# C-05_LPDDR4_x.net
KiCad netlist of a schematic drawn in Altium Designer
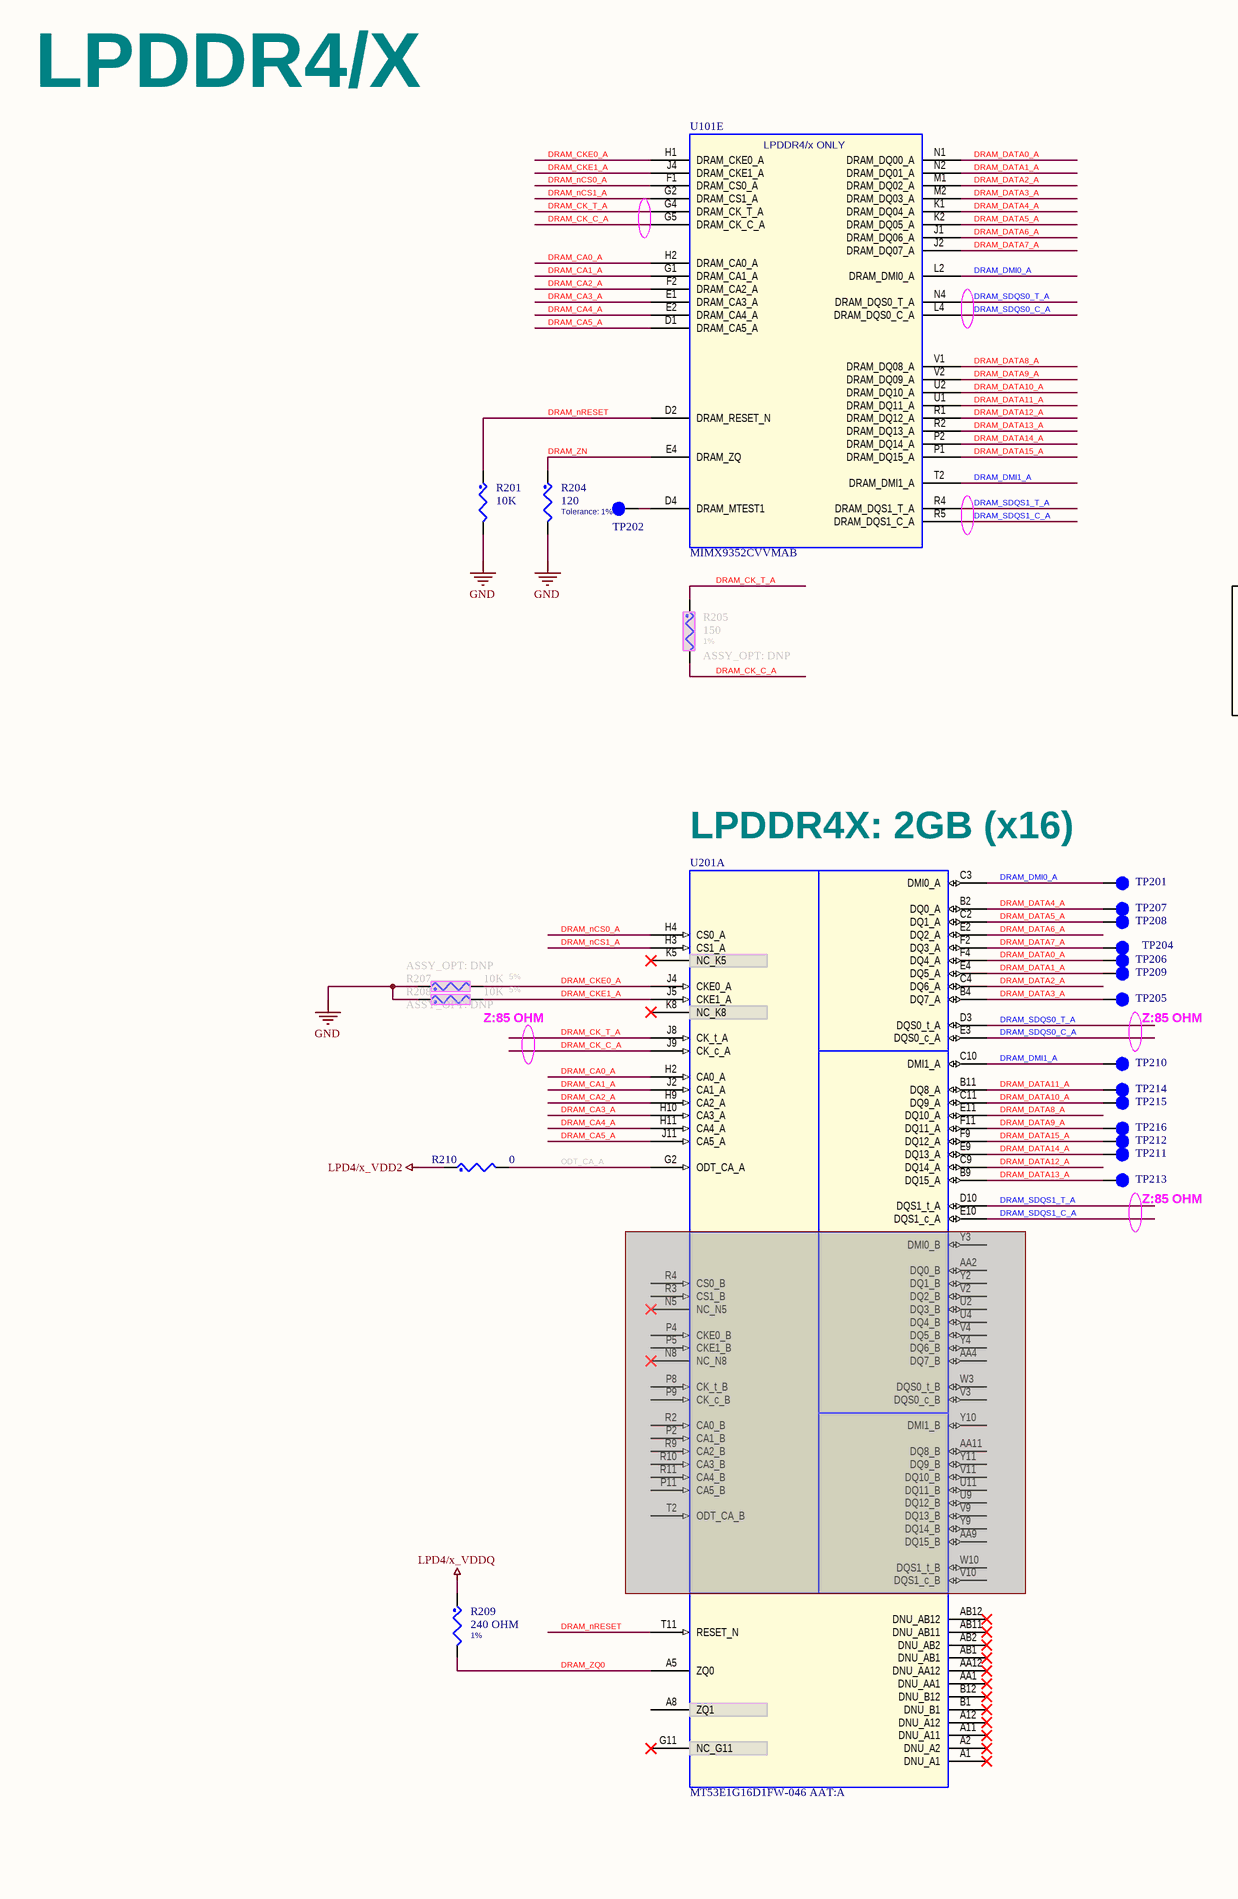
[diagram p0: C-05 LPDDR4_x.SchDoc, left]
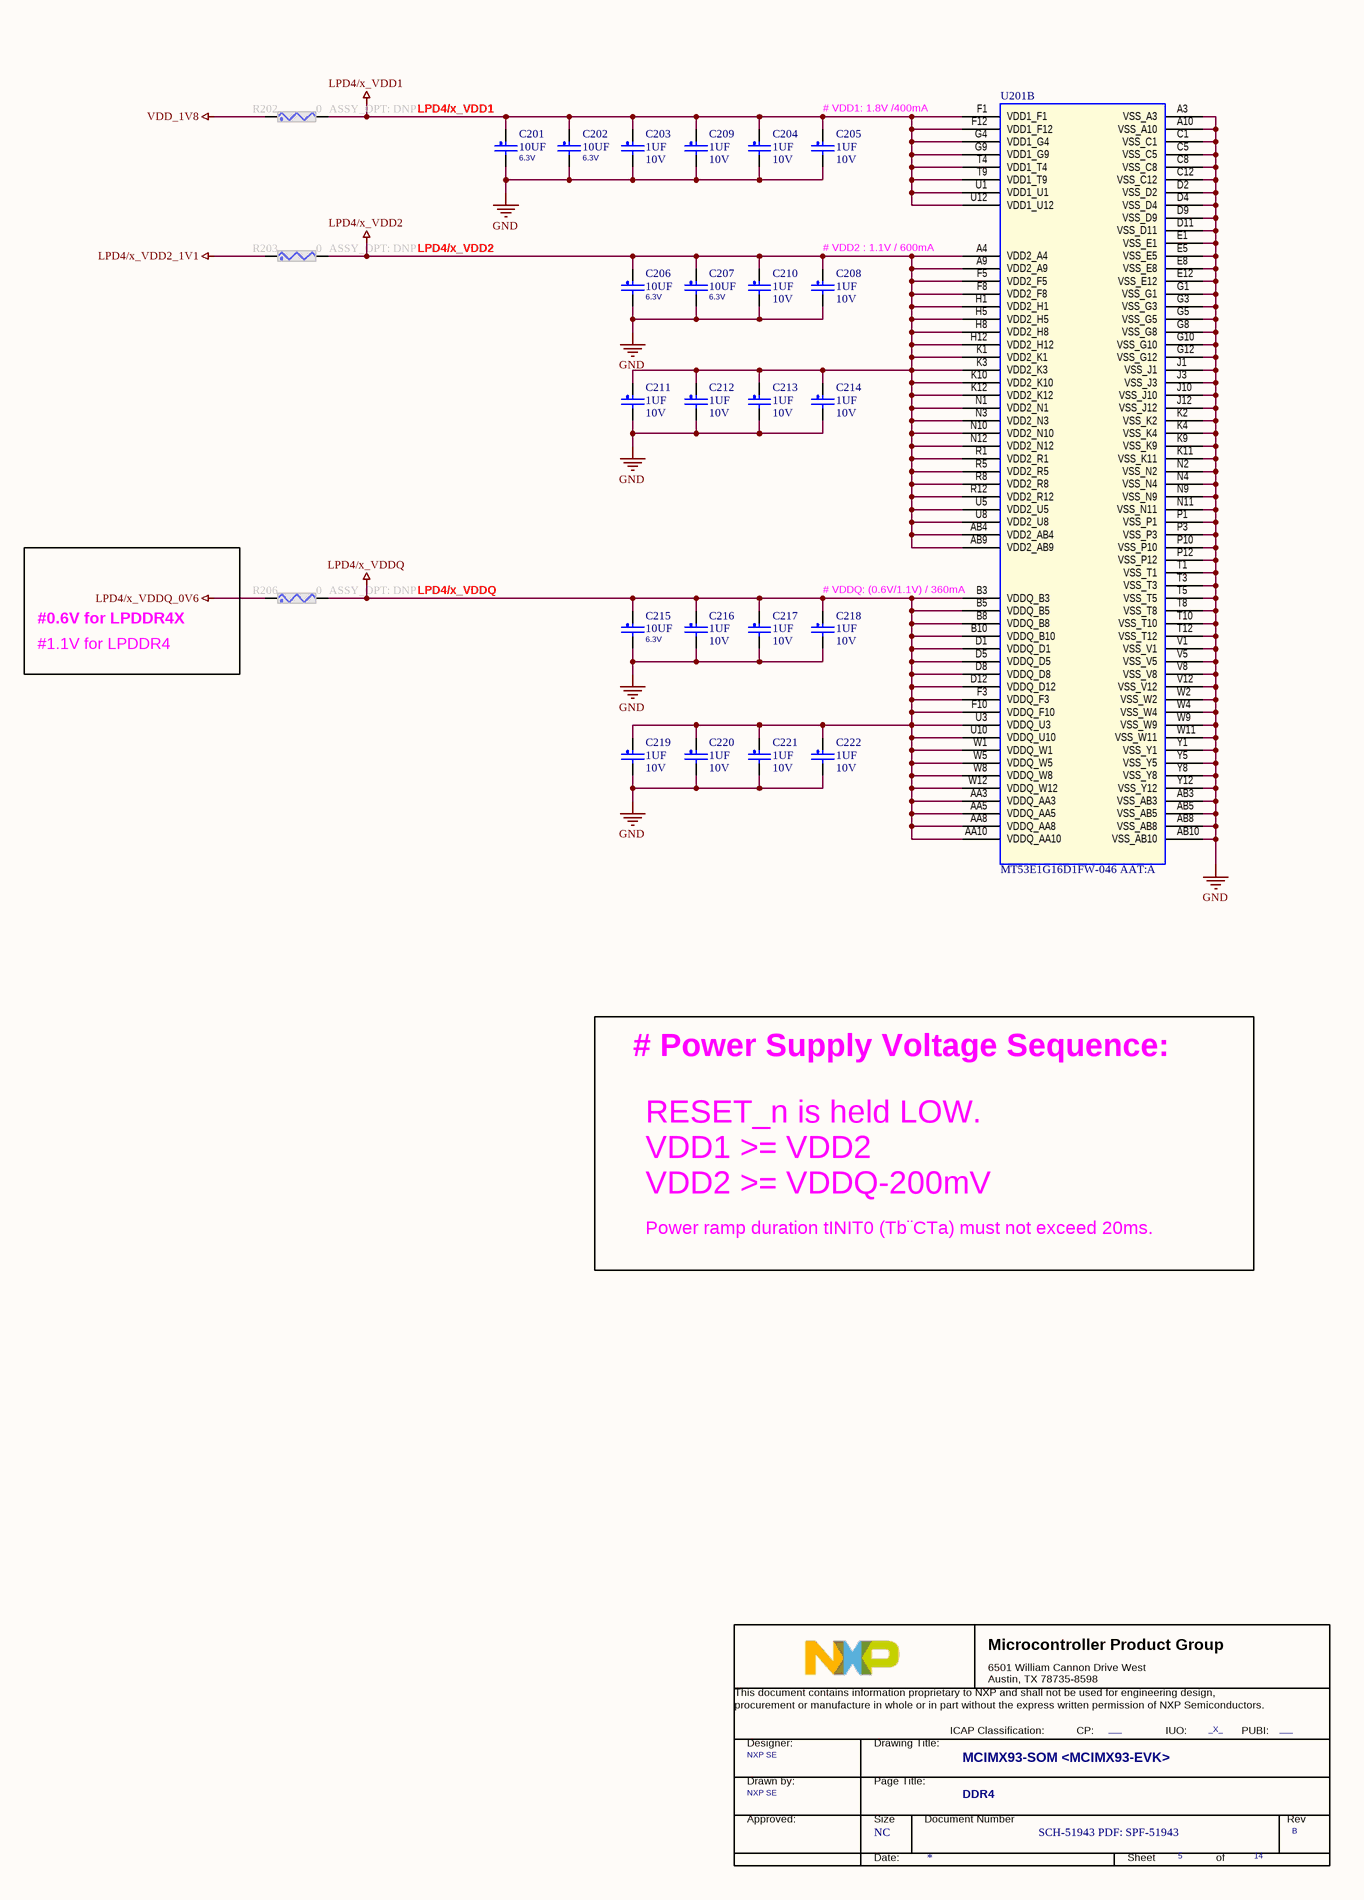
[diagram p1: C-05 LPDDR4_x.SchDoc, right]

(export (version "E")
  (design (tool "Eeschema 10.0.6"))
  (components
    (comp (ref "C201")
      (value "10UF")
      (footprint "0402_CC")
      (description "CAP CER 10UF 6.3V 20% X5R 0402")
      (fields (field (name "TOLERANCE") "20%") (field (name "VOLTAGE") "6.3V"))
      (libsource (lib "*") (part "CAP_NP"))
    )
    (comp (ref "C202")
      (value "10UF")
      (footprint "0402_CC")
      (description "CAP CER 10UF 6.3V 20% X5R 0402")
      (fields (field (name "TOLERANCE") "20%") (field (name "VOLTAGE") "6.3V"))
      (libsource (lib "*") (part "CAP_NP"))
    )
    (comp (ref "C203")
      (value "1UF")
      (footprint "0201_CC")
      (description "CAP CER 1.0uF 10V 10% X5R 0201")
      (fields (field (name "VOLTAGE") "10V") (field (name "TOLERANCE") "10%"))
      (libsource (lib "*") (part "CAP_NP"))
    )
    (comp (ref "C204")
      (value "1UF")
      (footprint "0201_CC")
      (description "CAP CER 1.0uF 10V 10% X5R 0201")
      (fields (field (name "TOLERANCE") "10%") (field (name "VOLTAGE") "10V"))
      (libsource (lib "*") (part "CAP_NP"))
    )
    (comp (ref "C205")
      (value "1UF")
      (footprint "0201_CC")
      (description "CAP CER 1.0uF 10V 10% X5R 0201")
      (fields (field (name "VOLTAGE") "10V") (field (name "TOLERANCE") "10%"))
      (libsource (lib "*") (part "CAP_NP"))
    )
    (comp (ref "C206")
      (value "10UF")
      (footprint "0402_CC")
      (description "CAP CER 10UF 6.3V 20% X5R 0402")
      (fields (field (name "TOLERANCE") "20%") (field (name "VOLTAGE") "6.3V"))
      (libsource (lib "*") (part "CAP_NP"))
    )
    (comp (ref "C207")
      (value "10UF")
      (footprint "0402_CC")
      (description "CAP CER 10UF 6.3V 20% X5R 0402")
      (fields (field (name "TOLERANCE") "20%") (field (name "VOLTAGE") "6.3V"))
      (libsource (lib "*") (part "CAP_NP"))
    )
    (comp (ref "C208")
      (value "1UF")
      (footprint "0201_CC")
      (description "CAP CER 1.0uF 10V 10% X5R 0201")
      (fields (field (name "TOLERANCE") "10%") (field (name "VOLTAGE") "10V"))
      (libsource (lib "*") (part "CAP_NP"))
    )
    (comp (ref "C209")
      (value "1UF")
      (footprint "0201_CC")
      (description "CAP CER 1.0uF 10V 10% X5R 0201")
      (fields (field (name "TOLERANCE") "10%") (field (name "VOLTAGE") "10V"))
      (libsource (lib "*") (part "CAP_NP"))
    )
    (comp (ref "C210")
      (value "1UF")
      (footprint "0201_CC")
      (description "CAP CER 1.0uF 10V 10% X5R 0201")
      (fields (field (name "TOLERANCE") "10%") (field (name "VOLTAGE") "10V"))
      (libsource (lib "*") (part "CAP_NP"))
    )
    (comp (ref "C211")
      (value "1UF")
      (footprint "0201_CC")
      (description "CAP CER 1.0uF 10V 10% X5R 0201")
      (fields (field (name "VOLTAGE") "10V") (field (name "TOLERANCE") "10%"))
      (libsource (lib "*") (part "CAP_NP"))
    )
    (comp (ref "C212")
      (value "1UF")
      (footprint "0201_CC")
      (description "CAP CER 1.0uF 10V 10% X5R 0201")
      (fields (field (name "VOLTAGE") "10V") (field (name "TOLERANCE") "10%"))
      (libsource (lib "*") (part "CAP_NP"))
    )
    (comp (ref "C213")
      (value "1UF")
      (footprint "0201_CC")
      (description "CAP CER 1.0uF 10V 10% X5R 0201")
      (fields (field (name "VOLTAGE") "10V") (field (name "TOLERANCE") "10%"))
      (libsource (lib "*") (part "CAP_NP"))
    )
    (comp (ref "C214")
      (value "1UF")
      (footprint "0201_CC")
      (description "CAP CER 1.0uF 10V 10% X5R 0201")
      (fields (field (name "TOLERANCE") "10%") (field (name "VOLTAGE") "10V"))
      (libsource (lib "*") (part "CAP_NP"))
    )
    (comp (ref "C215")
      (value "10UF")
      (footprint "0402_CC")
      (description "CAP CER 10UF 6.3V 20% X5R 0402")
      (fields (field (name "TOLERANCE") "20%") (field (name "VOLTAGE") "6.3V"))
      (libsource (lib "*") (part "CAP_NP"))
    )
    (comp (ref "C216")
      (value "1UF")
      (footprint "0201_CC")
      (description "CAP CER 1.0uF 10V 10% X5R 0201")
      (fields (field (name "VOLTAGE") "10V") (field (name "TOLERANCE") "10%"))
      (libsource (lib "*") (part "CAP_NP"))
    )
    (comp (ref "C217")
      (value "1UF")
      (footprint "0201_CC")
      (description "CAP CER 1.0uF 10V 10% X5R 0201")
      (fields (field (name "TOLERANCE") "10%") (field (name "VOLTAGE") "10V"))
      (libsource (lib "*") (part "CAP_NP"))
    )
    (comp (ref "C218")
      (value "1UF")
      (footprint "0201_CC")
      (description "CAP CER 1.0uF 10V 10% X5R 0201")
      (fields (field (name "VOLTAGE") "10V") (field (name "TOLERANCE") "10%"))
      (libsource (lib "*") (part "CAP_NP"))
    )
    (comp (ref "C219")
      (value "1UF")
      (footprint "0201_CC")
      (description "CAP CER 1.0uF 10V 10% X5R 0201")
      (fields (field (name "TOLERANCE") "10%") (field (name "VOLTAGE") "10V"))
      (libsource (lib "*") (part "CAP_NP"))
    )
    (comp (ref "C220")
      (value "1UF")
      (footprint "0201_CC")
      (description "CAP CER 1.0uF 10V 10% X5R 0201")
      (fields (field (name "VOLTAGE") "10V") (field (name "TOLERANCE") "10%"))
      (libsource (lib "*") (part "CAP_NP"))
    )
    (comp (ref "C221")
      (value "1UF")
      (footprint "0201_CC")
      (description "CAP CER 1.0uF 10V 10% X5R 0201")
      (fields (field (name "TOLERANCE") "10%") (field (name "VOLTAGE") "10V"))
      (libsource (lib "*") (part "CAP_NP"))
    )
    (comp (ref "C222")
      (value "1UF")
      (footprint "0201_CC")
      (description "CAP CER 1.0uF 10V 10% X5R 0201")
      (fields (field (name "VOLTAGE") "10V") (field (name "TOLERANCE") "10%"))
      (libsource (lib "*") (part "CAP_NP"))
    )
    (comp (ref "R201")
      (value "10K")
      (footprint "0402_CC")
      (description "RES MF 10K 1/16W 5% 0402")
      (fields (field (name "TOLERANCE") "5%"))
      (libsource (lib "*") (part "RES"))
    )
    (comp (ref "R202")
      (value "0")
      (footprint "0603_CC")
      (description "RES MF ZERO OHM 1/10W -- 0603")
      (fields (field (name "ASSY_OPT") "DNP"))
      (libsource (lib "*") (part "RES"))
    )
    (comp (ref "R203")
      (value "0")
      (footprint "0603_CC")
      (description "RES MF ZERO OHM 1/10W -- 0603")
      (fields (field (name "ASSY_OPT") "DNP"))
      (libsource (lib "*") (part "RES"))
    )
    (comp (ref "R204")
      (value "120")
      (footprint "0402_CC")
      (description "RES MF 120 OHM 1/10W 1% AEC-Q200 0402")
      (fields (field (name "VOLTAGE") "1/10W") (field (name "TOLERANCE") "1%"))
      (libsource (lib "*") (part "RES"))
    )
    (comp (ref "R205")
      (value "150")
      (footprint "0402_CC")
      (description "RES MF 150 OHM 1/16W 1% 0402")
      (fields (field (name "ASSY_OPT") "DNP") (field (name "TOLERANCE") "1%"))
      (libsource (lib "*") (part "RES"))
    )
    (comp (ref "R206")
      (value "0")
      (footprint "0603_CC")
      (description "RES MF ZERO OHM 1/10W -- 0603")
      (fields (field (name "ASSY_OPT") "DNP"))
      (libsource (lib "*") (part "RES"))
    )
    (comp (ref "R207")
      (value "10K")
      (footprint "0402_CC")
      (description "RES MF 10K 1/16W 5% 0402")
      (fields (field (name "ASSY_OPT") "DNP") (field (name "TOLERANCE") "5%"))
      (libsource (lib "*") (part "RES"))
    )
    (comp (ref "R208")
      (value "10K")
      (footprint "0402_CC")
      (description "RES MF 10K 1/16W 5% 0402")
      (fields (field (name "ASSY_OPT") "DNP") (field (name "TOLERANCE") "5%"))
      (libsource (lib "*") (part "RES"))
    )
    (comp (ref "R209")
      (value "240 OHM")
      (footprint "0201_CC")
      (description "RES MF 240 OHM 1/20W 1% 0201")
      (fields (field (name "VOLTAGE") "25V") (field (name "TOLERANCE") "1%"))
      (libsource (lib "*") (part "RES"))
    )
    (comp (ref "R210")
      (value "0")
      (footprint "0402_CC")
      (description "RES MF ZERO OHM 1/16W 5% 0402")
      (fields (field (name "VOLTAGE") "1/16W") (field (name "TOLERANCE") "5%"))
      (libsource (lib "*") (part "RES"))
    )
    (comp (ref "TP201")
      (value "TPAD_015")
      (footprint "TPAD_015")
      (description "TEST POINT PAD 15MIL DIA SMT, NO PART TO ORDER")
      (libsource (lib "*") (part "TESTLOOP"))
    )
    (comp (ref "TP202")
      (value "tpad_020")
      (footprint "tpad_020")
      (description "TEST POINT PAD 0.5MM DIA SMT, NO PART TO ORDER")
      (libsource (lib "*") (part "TESTLOOP"))
    )
    (comp (ref "TP204")
      (value "TPAD_015")
      (footprint "TPAD_015")
      (description "TEST POINT PAD 15MIL DIA SMT, NO PART TO ORDER")
      (libsource (lib "*") (part "TESTLOOP"))
    )
    (comp (ref "TP205")
      (value "TPAD_015")
      (footprint "TPAD_015")
      (description "TEST POINT PAD 15MIL DIA SMT, NO PART TO ORDER")
      (libsource (lib "*") (part "TESTLOOP"))
    )
    (comp (ref "TP206")
      (value "TPAD_015")
      (footprint "TPAD_015")
      (description "TEST POINT PAD 15MIL DIA SMT, NO PART TO ORDER")
      (libsource (lib "*") (part "TESTLOOP"))
    )
    (comp (ref "TP207")
      (value "TPAD_015")
      (footprint "TPAD_015")
      (description "TEST POINT PAD 15MIL DIA SMT, NO PART TO ORDER")
      (libsource (lib "*") (part "TESTLOOP"))
    )
    (comp (ref "TP208")
      (value "TPAD_015")
      (footprint "TPAD_015")
      (description "TEST POINT PAD 15MIL DIA SMT, NO PART TO ORDER")
      (libsource (lib "*") (part "TESTLOOP"))
    )
    (comp (ref "TP209")
      (value "TPAD_015")
      (footprint "TPAD_015")
      (description "TEST POINT PAD 15MIL DIA SMT, NO PART TO ORDER")
      (libsource (lib "*") (part "TESTLOOP"))
    )
    (comp (ref "TP210")
      (value "TPAD_015")
      (footprint "TPAD_015")
      (description "TEST POINT PAD 15MIL DIA SMT, NO PART TO ORDER")
      (libsource (lib "*") (part "TESTLOOP"))
    )
    (comp (ref "TP211")
      (value "TPAD_015")
      (footprint "TPAD_015")
      (description "TEST POINT PAD 15MIL DIA SMT, NO PART TO ORDER")
      (libsource (lib "*") (part "TESTLOOP"))
    )
    (comp (ref "TP212")
      (value "TPAD_015")
      (footprint "TPAD_015")
      (description "TEST POINT PAD 15MIL DIA SMT, NO PART TO ORDER")
      (libsource (lib "*") (part "TESTLOOP"))
    )
    (comp (ref "TP213")
      (value "TPAD_015")
      (footprint "TPAD_015")
      (description "TEST POINT PAD 15MIL DIA SMT, NO PART TO ORDER")
      (libsource (lib "*") (part "TESTLOOP"))
    )
    (comp (ref "TP214")
      (value "TPAD_015")
      (footprint "TPAD_015")
      (description "TEST POINT PAD 15MIL DIA SMT, NO PART TO ORDER")
      (libsource (lib "*") (part "TESTLOOP"))
    )
    (comp (ref "TP215")
      (value "TPAD_015")
      (footprint "TPAD_015")
      (description "TEST POINT PAD 15MIL DIA SMT, NO PART TO ORDER")
      (libsource (lib "*") (part "TESTLOOP"))
    )
    (comp (ref "TP216")
      (value "TPAD_015")
      (footprint "TPAD_015")
      (description "TEST POINT PAD 15MIL DIA SMT, NO PART TO ORDER")
      (libsource (lib "*") (part "TESTLOOP"))
    )
    (comp (ref "U101")
      (value "MIMX9352CVVMAB")
      (footprint "SKT_BGA306_0P5_SQ16P23_ELAST")
      (description "SUBASSEMBLY SKT 306 BGA ELASTOMER SMT 0.5MM 395H AU + IC CPU 1.7GHz -- FCBGA306")
      (libsource (lib "*") (part "MIMX9352DVNxLAA"))
    )
    (comp (ref "U201")
      (value "MT53E1G16D1FW-046 AAT:A")
      (footprint "bga200_0p65x0p8_10x14p5")
      (description "IC MEM LPDDR4/LPDDR4X SDRAM 1GX16 1.1V AEC-Q100 TFBGA200")
      (fields (field (name "VOLTAGE") "1.1V"))
      (libsource (lib "*") (part "MT53B768M32D4NQ_200P"))
    )
  )
  (nets
    (net (code "1") (name "/DRAM_CA0_A") (class "Default")
      (node (ref "U101") (pin "H2") (pinfunction "DRAM_CA0_A_H2") (pintype "passive"))
      (node (ref "U201") (pin "H2") (pinfunction "CA0_A_H2") (pintype "input"))
    )
    (net (code "2") (name "/DRAM_CA1_A") (class "Default")
      (node (ref "U101") (pin "G1") (pinfunction "DRAM_CA1_A_G1") (pintype "passive"))
      (node (ref "U201") (pin "J2") (pinfunction "CA1_A_J2") (pintype "input"))
    )
    (net (code "3") (name "/DRAM_CA2_A") (class "Default")
      (node (ref "U101") (pin "F2") (pinfunction "DRAM_CA2_A_F2") (pintype "passive"))
      (node (ref "U201") (pin "H9") (pinfunction "CA2_A_H9") (pintype "input"))
    )
    (net (code "4") (name "/DRAM_CA3_A") (class "Default")
      (node (ref "U101") (pin "E1") (pinfunction "DRAM_CA3_A_E1") (pintype "passive"))
      (node (ref "U201") (pin "H10") (pinfunction "CA3_A_H10") (pintype "input"))
    )
    (net (code "5") (name "/DRAM_CA4_A") (class "Default")
      (node (ref "U101") (pin "E2") (pinfunction "DRAM_CA4_A_E2") (pintype "passive"))
      (node (ref "U201") (pin "H11") (pinfunction "CA4_A_H11") (pintype "input"))
    )
    (net (code "6") (name "/DRAM_CA5_A") (class "Default")
      (node (ref "U101") (pin "D1") (pinfunction "DRAM_CA5_A_D1") (pintype "passive"))
      (node (ref "U201") (pin "J11") (pinfunction "CA5_A_J11") (pintype "input"))
    )
    (net (code "7") (name "/DRAM_CKE0_A") (class "Default")
      (node (ref "R207") (pin "2") (pinfunction "2_2") (pintype "passive"))
      (node (ref "U101") (pin "H1") (pinfunction "DRAM_CKE0_A_H1") (pintype "passive"))
      (node (ref "U201") (pin "J4") (pinfunction "CKE0_A_J4") (pintype "input"))
    )
    (net (code "8") (name "/DRAM_CKE1_A") (class "Default")
      (node (ref "R208") (pin "2") (pinfunction "2_2") (pintype "passive"))
      (node (ref "U101") (pin "J4") (pinfunction "DRAM_CKE1_A_J4") (pintype "passive"))
      (node (ref "U201") (pin "J5") (pinfunction "CKE1_A_J5") (pintype "input"))
    )
    (net (code "9") (name "/DRAM_CK_C_A") (class "Default")
      (node (ref "R205") (pin "2") (pinfunction "2_2") (pintype "passive"))
      (node (ref "U101") (pin "G5") (pinfunction "DRAM_CK_C_A_G5") (pintype "passive"))
      (node (ref "U201") (pin "J9") (pinfunction "CK_c_A_J9") (pintype "input"))
    )
    (net (code "10") (name "/DRAM_CK_T_A") (class "Default")
      (node (ref "R205") (pin "1") (pinfunction "1_1") (pintype "passive"))
      (node (ref "U101") (pin "G4") (pinfunction "DRAM_CK_T_A_G4") (pintype "passive"))
      (node (ref "U201") (pin "J8") (pinfunction "CK_t_A_J8") (pintype "input"))
    )
    (net (code "11") (name "/DRAM_DATA0_A") (class "Default")
      (node (ref "TP206") (pin "1") (pinfunction "Pin1_1") (pintype "passive"))
      (node (ref "U101") (pin "N1") (pinfunction "DRAM_DQ00_A_N1") (pintype "passive"))
      (node (ref "U201") (pin "F4") (pinfunction "DQ4_A_F4") (pintype "bidirectional"))
    )
    (net (code "12") (name "/DRAM_DATA1_A") (class "Default")
      (node (ref "TP209") (pin "1") (pinfunction "Pin1_1") (pintype "passive"))
      (node (ref "U101") (pin "N2") (pinfunction "DRAM_DQ01_A_N2") (pintype "passive"))
      (node (ref "U201") (pin "E4") (pinfunction "DQ5_A_E4") (pintype "bidirectional"))
    )
    (net (code "13") (name "/DRAM_DATA2_A") (class "Default")
      (node (ref "U101") (pin "M1") (pinfunction "DRAM_DQ02_A_M1") (pintype "passive"))
      (node (ref "U201") (pin "C4") (pinfunction "DQ6_A_C4") (pintype "bidirectional"))
    )
    (net (code "14") (name "/DRAM_DATA3_A") (class "Default")
      (node (ref "TP205") (pin "1") (pinfunction "Pin1_1") (pintype "passive"))
      (node (ref "U101") (pin "M2") (pinfunction "DRAM_DQ03_A_M2") (pintype "passive"))
      (node (ref "U201") (pin "B4") (pinfunction "DQ7_A_B4") (pintype "bidirectional"))
    )
    (net (code "15") (name "/DRAM_DATA4_A") (class "Default")
      (node (ref "TP207") (pin "1") (pinfunction "Pin1_1") (pintype "passive"))
      (node (ref "U101") (pin "K1") (pinfunction "DRAM_DQ04_A_K1") (pintype "passive"))
      (node (ref "U201") (pin "B2") (pinfunction "DQ0_A_B2") (pintype "bidirectional"))
    )
    (net (code "16") (name "/DRAM_DATA5_A") (class "Default")
      (node (ref "TP208") (pin "1") (pinfunction "Pin1_1") (pintype "passive"))
      (node (ref "U101") (pin "K2") (pinfunction "DRAM_DQ05_A_K2") (pintype "passive"))
      (node (ref "U201") (pin "C2") (pinfunction "DQ1_A_C2") (pintype "bidirectional"))
    )
    (net (code "17") (name "/DRAM_DATA6_A") (class "Default")
      (node (ref "U101") (pin "J1") (pinfunction "DRAM_DQ06_A_J1") (pintype "passive"))
      (node (ref "U201") (pin "E2") (pinfunction "DQ2_A_E2") (pintype "bidirectional"))
    )
    (net (code "18") (name "/DRAM_DATA7_A") (class "Default")
      (node (ref "TP204") (pin "1") (pinfunction "Pin1_1") (pintype "passive"))
      (node (ref "U101") (pin "J2") (pinfunction "DRAM_DQ07_A_J2") (pintype "passive"))
      (node (ref "U201") (pin "F2") (pinfunction "DQ3_A_F2") (pintype "bidirectional"))
    )
    (net (code "19") (name "/DRAM_DATA8_A") (class "Default")
      (node (ref "U101") (pin "V1") (pinfunction "DRAM_DQ08_A_V1") (pintype "passive"))
      (node (ref "U201") (pin "E11") (pinfunction "DQ10_A_E11") (pintype "bidirectional"))
    )
    (net (code "20") (name "/DRAM_DATA9_A") (class "Default")
      (node (ref "TP216") (pin "1") (pinfunction "Pin1_1") (pintype "passive"))
      (node (ref "U101") (pin "V2") (pinfunction "DRAM_DQ09_A_V2") (pintype "passive"))
      (node (ref "U201") (pin "F11") (pinfunction "DQ11_A_F11") (pintype "bidirectional"))
    )
    (net (code "21") (name "/DRAM_DATA10_A") (class "Default")
      (node (ref "TP215") (pin "1") (pinfunction "Pin1_1") (pintype "passive"))
      (node (ref "U101") (pin "U2") (pinfunction "DRAM_DQ10_A_U2") (pintype "passive"))
      (node (ref "U201") (pin "C11") (pinfunction "DQ9_A_C11") (pintype "bidirectional"))
    )
    (net (code "22") (name "/DRAM_DATA11_A") (class "Default")
      (node (ref "TP214") (pin "1") (pinfunction "Pin1_1") (pintype "passive"))
      (node (ref "U101") (pin "U1") (pinfunction "DRAM_DQ11_A_U1") (pintype "passive"))
      (node (ref "U201") (pin "B11") (pinfunction "DQ8_A_B11") (pintype "bidirectional"))
    )
    (net (code "23") (name "/DRAM_DATA12_A") (class "Default")
      (node (ref "U101") (pin "R1") (pinfunction "DRAM_DQ12_A_R1") (pintype "passive"))
      (node (ref "U201") (pin "C9") (pinfunction "DQ14_A_C9") (pintype "bidirectional"))
    )
    (net (code "24") (name "/DRAM_DATA13_A") (class "Default")
      (node (ref "TP213") (pin "1") (pinfunction "Pin1_1") (pintype "passive"))
      (node (ref "U101") (pin "R2") (pinfunction "DRAM_DQ13_A_R2") (pintype "passive"))
      (node (ref "U201") (pin "B9") (pinfunction "DQ15_A_B9") (pintype "bidirectional"))
    )
    (net (code "25") (name "/DRAM_DATA14_A") (class "Default")
      (node (ref "TP211") (pin "1") (pinfunction "Pin1_1") (pintype "passive"))
      (node (ref "U101") (pin "P2") (pinfunction "DRAM_DQ14_A_P2") (pintype "passive"))
      (node (ref "U201") (pin "E9") (pinfunction "DQ13_A_E9") (pintype "bidirectional"))
    )
    (net (code "26") (name "/DRAM_DATA15_A") (class "Default")
      (node (ref "TP212") (pin "1") (pinfunction "Pin1_1") (pintype "passive"))
      (node (ref "U101") (pin "P1") (pinfunction "DRAM_DQ15_A_P1") (pintype "passive"))
      (node (ref "U201") (pin "F9") (pinfunction "DQ12_A_F9") (pintype "bidirectional"))
    )
    (net (code "27") (name "/DRAM_DMI0_A") (class "Default")
      (node (ref "TP201") (pin "1") (pinfunction "Pin1_1") (pintype "passive"))
      (node (ref "U101") (pin "L2") (pinfunction "DRAM_DMI0_A_L2") (pintype "passive"))
      (node (ref "U201") (pin "C3") (pinfunction "DMI0_A_C3") (pintype "bidirectional"))
    )
    (net (code "28") (name "/DRAM_DMI1_A") (class "Default")
      (node (ref "TP210") (pin "1") (pinfunction "Pin1_1") (pintype "passive"))
      (node (ref "U101") (pin "T2") (pinfunction "DRAM_DMI1_A_T2") (pintype "passive"))
      (node (ref "U201") (pin "C10") (pinfunction "DMI1_A_C10") (pintype "bidirectional"))
    )
    (net (code "29") (name "/DRAM_SDQS0_C_A") (class "Default")
      (node (ref "U101") (pin "L4") (pinfunction "DRAM_DQS0_C_A_L4") (pintype "passive"))
      (node (ref "U201") (pin "E3") (pinfunction "DQS0_c_A_E3") (pintype "bidirectional"))
    )
    (net (code "30") (name "/DRAM_SDQS0_T_A") (class "Default")
      (node (ref "U101") (pin "N4") (pinfunction "DRAM_DQS0_T_A_N4") (pintype "passive"))
      (node (ref "U201") (pin "D3") (pinfunction "DQS0_t_A_D3") (pintype "bidirectional"))
    )
    (net (code "31") (name "/DRAM_SDQS1_C_A") (class "Default")
      (node (ref "U101") (pin "R5") (pinfunction "DRAM_DQS1_C_A_R5") (pintype "passive"))
      (node (ref "U201") (pin "E10") (pinfunction "DQS1_c_A_E10") (pintype "bidirectional"))
    )
    (net (code "32") (name "/DRAM_SDQS1_T_A") (class "Default")
      (node (ref "U101") (pin "R4") (pinfunction "DRAM_DQS1_T_A_R4") (pintype "passive"))
      (node (ref "U201") (pin "D10") (pinfunction "DQS1_t_A_D10") (pintype "bidirectional"))
    )
    (net (code "33") (name "/DRAM_ZN") (class "Default")
      (node (ref "R204") (pin "1") (pinfunction "1_1") (pintype "passive"))
      (node (ref "U101") (pin "E4") (pinfunction "DRAM_ZQ_E4") (pintype "passive"))
    )
    (net (code "34") (name "/DRAM_ZQ0") (class "Default")
      (node (ref "R209") (pin "2") (pinfunction "2_2") (pintype "passive"))
      (node (ref "U201") (pin "A5") (pinfunction "ZQ0_A5") (pintype "passive"))
    )
    (net (code "35") (name "/DRAM_nCS0_A") (class "Default")
      (node (ref "U101") (pin "F1") (pinfunction "DRAM_CS0_A_F1") (pintype "passive"))
      (node (ref "U201") (pin "H4") (pinfunction "CS0_A_H4") (pintype "input"))
    )
    (net (code "36") (name "/DRAM_nCS1_A") (class "Default")
      (node (ref "U101") (pin "G2") (pinfunction "DRAM_CS1_A_G2") (pintype "passive"))
      (node (ref "U201") (pin "H3") (pinfunction "CS1_A_H3") (pintype "input"))
    )
    (net (code "37") (name "/DRAM_nRESET") (class "Default")
      (node (ref "R201") (pin "1") (pinfunction "1_1") (pintype "passive"))
      (node (ref "U101") (pin "D2") (pinfunction "DRAM_RESET_N_D2") (pintype "passive"))
      (node (ref "U201") (pin "T11") (pinfunction "RESET_N_T11") (pintype "input"))
    )
    (net (code "38") (name "/ODT_CA_A") (class "Default")
      (node (ref "R210") (pin "2") (pinfunction "2_2") (pintype "passive"))
      (node (ref "U201") (pin "G2") (pinfunction "ODT_CA_A_G2") (pintype "input"))
    )
    (net (code "39") (name "GND") (class "Default")
      (node (ref "C201") (pin "2") (pinfunction "2_2") (pintype "passive"))
      (node (ref "C202") (pin "2") (pinfunction "2_2") (pintype "passive"))
      (node (ref "C203") (pin "2") (pinfunction "2_2") (pintype "passive"))
      (node (ref "C204") (pin "2") (pinfunction "2_2") (pintype "passive"))
      (node (ref "C205") (pin "2") (pinfunction "2_2") (pintype "passive"))
      (node (ref "C206") (pin "2") (pinfunction "2_2") (pintype "passive"))
      (node (ref "C207") (pin "2") (pinfunction "2_2") (pintype "passive"))
      (node (ref "C208") (pin "2") (pinfunction "2_2") (pintype "passive"))
      (node (ref "C209") (pin "2") (pinfunction "2_2") (pintype "passive"))
      (node (ref "C210") (pin "2") (pinfunction "2_2") (pintype "passive"))
      (node (ref "C211") (pin "2") (pinfunction "2_2") (pintype "passive"))
      (node (ref "C212") (pin "2") (pinfunction "2_2") (pintype "passive"))
      (node (ref "C213") (pin "2") (pinfunction "2_2") (pintype "passive"))
      (node (ref "C214") (pin "2") (pinfunction "2_2") (pintype "passive"))
      (node (ref "C215") (pin "2") (pinfunction "2_2") (pintype "passive"))
      (node (ref "C216") (pin "2") (pinfunction "2_2") (pintype "passive"))
      (node (ref "C217") (pin "2") (pinfunction "2_2") (pintype "passive"))
      (node (ref "C218") (pin "2") (pinfunction "2_2") (pintype "passive"))
      (node (ref "C219") (pin "2") (pinfunction "2_2") (pintype "passive"))
      (node (ref "C220") (pin "2") (pinfunction "2_2") (pintype "passive"))
      (node (ref "C221") (pin "2") (pinfunction "2_2") (pintype "passive"))
      (node (ref "C222") (pin "2") (pinfunction "2_2") (pintype "passive"))
      (node (ref "R201") (pin "2") (pinfunction "2_2") (pintype "passive"))
      (node (ref "R204") (pin "2") (pinfunction "2_2") (pintype "passive"))
      (node (ref "R207") (pin "1") (pinfunction "1_1") (pintype "passive"))
      (node (ref "R208") (pin "1") (pinfunction "1_1") (pintype "passive"))
      (node (ref "U201") (pin "A10") (pinfunction "VSS_A10_A10") (pintype "power_in"))
      (node (ref "U201") (pin "A3") (pinfunction "VSS_A3_A3") (pintype "power_in"))
      (node (ref "U201") (pin "AB10") (pinfunction "VSS_AB10_AB10") (pintype "power_in"))
      (node (ref "U201") (pin "AB3") (pinfunction "VSS_AB3_AB3") (pintype "power_in"))
      (node (ref "U201") (pin "AB5") (pinfunction "VSS_AB5_AB5") (pintype "power_in"))
      (node (ref "U201") (pin "AB8") (pinfunction "VSS_AB8_AB8") (pintype "power_in"))
      (node (ref "U201") (pin "C1") (pinfunction "VSS_C1_C1") (pintype "power_in"))
      (node (ref "U201") (pin "C12") (pinfunction "VSS_C12_C12") (pintype "power_in"))
      (node (ref "U201") (pin "C5") (pinfunction "VSS_C5_C5") (pintype "power_in"))
      (node (ref "U201") (pin "C8") (pinfunction "VSS_C8_C8") (pintype "power_in"))
      (node (ref "U201") (pin "D11") (pinfunction "VSS_D11_D11") (pintype "power_in"))
      (node (ref "U201") (pin "D2") (pinfunction "VSS_D2_D2") (pintype "power_in"))
      (node (ref "U201") (pin "D4") (pinfunction "VSS_D4_D4") (pintype "power_in"))
      (node (ref "U201") (pin "D9") (pinfunction "VSS_D9_D9") (pintype "power_in"))
      (node (ref "U201") (pin "E1") (pinfunction "VSS_E1_E1") (pintype "power_in"))
      (node (ref "U201") (pin "E12") (pinfunction "VSS_E12_E12") (pintype "power_in"))
      (node (ref "U201") (pin "E5") (pinfunction "VSS_E5_E5") (pintype "power_in"))
      (node (ref "U201") (pin "E8") (pinfunction "VSS_E8_E8") (pintype "power_in"))
      (node (ref "U201") (pin "G1") (pinfunction "VSS_G1_G1") (pintype "power_in"))
      (node (ref "U201") (pin "G10") (pinfunction "VSS_G10_G10") (pintype "power_in"))
      (node (ref "U201") (pin "G12") (pinfunction "VSS_G12_G12") (pintype "power_in"))
      (node (ref "U201") (pin "G3") (pinfunction "VSS_G3_G3") (pintype "power_in"))
      (node (ref "U201") (pin "G5") (pinfunction "VSS_G5_G5") (pintype "power_in"))
      (node (ref "U201") (pin "G8") (pinfunction "VSS_G8_G8") (pintype "power_in"))
      (node (ref "U201") (pin "J1") (pinfunction "VSS_J1_J1") (pintype "power_in"))
      (node (ref "U201") (pin "J10") (pinfunction "VSS_J10_J10") (pintype "power_in"))
      (node (ref "U201") (pin "J12") (pinfunction "VSS_J12_J12") (pintype "power_in"))
      (node (ref "U201") (pin "J3") (pinfunction "VSS_J3_J3") (pintype "power_in"))
      (node (ref "U201") (pin "K11") (pinfunction "VSS_K11_K11") (pintype "power_in"))
      (node (ref "U201") (pin "K2") (pinfunction "VSS_K2_K2") (pintype "power_in"))
      (node (ref "U201") (pin "K4") (pinfunction "VSS_K4_K4") (pintype "power_in"))
      (node (ref "U201") (pin "K9") (pinfunction "VSS_K9_K9") (pintype "power_in"))
      (node (ref "U201") (pin "N11") (pinfunction "VSS_N11_N11") (pintype "power_in"))
      (node (ref "U201") (pin "N2") (pinfunction "VSS_N2_N2") (pintype "power_in"))
      (node (ref "U201") (pin "N4") (pinfunction "VSS_N4_N4") (pintype "power_in"))
      (node (ref "U201") (pin "N9") (pinfunction "VSS_N9_N9") (pintype "power_in"))
      (node (ref "U201") (pin "P1") (pinfunction "VSS_P1_P1") (pintype "power_in"))
      (node (ref "U201") (pin "P10") (pinfunction "VSS_P10_P10") (pintype "power_in"))
      (node (ref "U201") (pin "P12") (pinfunction "VSS_P12_P12") (pintype "power_in"))
      (node (ref "U201") (pin "P3") (pinfunction "VSS_P3_P3") (pintype "power_in"))
      (node (ref "U201") (pin "T1") (pinfunction "VSS_T1_T1") (pintype "power_in"))
      (node (ref "U201") (pin "T10") (pinfunction "VSS_T10_T10") (pintype "power_in"))
      (node (ref "U201") (pin "T12") (pinfunction "VSS_T12_T12") (pintype "power_in"))
      (node (ref "U201") (pin "T3") (pinfunction "VSS_T3_T3") (pintype "power_in"))
      (node (ref "U201") (pin "T5") (pinfunction "VSS_T5_T5") (pintype "power_in"))
      (node (ref "U201") (pin "T8") (pinfunction "VSS_T8_T8") (pintype "power_in"))
      (node (ref "U201") (pin "V1") (pinfunction "VSS_V1_V1") (pintype "power_in"))
      (node (ref "U201") (pin "V12") (pinfunction "VSS_V12_V12") (pintype "power_in"))
      (node (ref "U201") (pin "V5") (pinfunction "VSS_V5_V5") (pintype "power_in"))
      (node (ref "U201") (pin "V8") (pinfunction "VSS_V8_V8") (pintype "power_in"))
      (node (ref "U201") (pin "W11") (pinfunction "VSS_W11_W11") (pintype "power_in"))
      (node (ref "U201") (pin "W2") (pinfunction "VSS_W2_W2") (pintype "power_in"))
      (node (ref "U201") (pin "W4") (pinfunction "VSS_W4_W4") (pintype "power_in"))
      (node (ref "U201") (pin "W9") (pinfunction "VSS_W9_W9") (pintype "power_in"))
      (node (ref "U201") (pin "Y1") (pinfunction "VSS_Y1_Y1") (pintype "power_in"))
      (node (ref "U201") (pin "Y12") (pinfunction "VSS_Y12_Y12") (pintype "power_in"))
      (node (ref "U201") (pin "Y5") (pinfunction "VSS_Y5_Y5") (pintype "power_in"))
      (node (ref "U201") (pin "Y8") (pinfunction "VSS_Y8_Y8") (pintype "power_in"))
    )
    (net (code "40") (name "LPD4{slash}x_VDD1") (class "Default")
      (node (ref "C201") (pin "1") (pinfunction "1_1") (pintype "passive"))
      (node (ref "C202") (pin "1") (pinfunction "1_1") (pintype "passive"))
      (node (ref "C203") (pin "1") (pinfunction "1_1") (pintype "passive"))
      (node (ref "C204") (pin "1") (pinfunction "1_1") (pintype "passive"))
      (node (ref "C205") (pin "1") (pinfunction "1_1") (pintype "passive"))
      (node (ref "C209") (pin "1") (pinfunction "1_1") (pintype "passive"))
      (node (ref "R202") (pin "2") (pinfunction "2_2") (pintype "passive"))
      (node (ref "U201") (pin "F1") (pinfunction "VDD1_F1_F1") (pintype "power_in"))
      (node (ref "U201") (pin "F12") (pinfunction "VDD1_F12_F12") (pintype "power_in"))
      (node (ref "U201") (pin "G4") (pinfunction "VDD1_G4_G4") (pintype "power_in"))
      (node (ref "U201") (pin "G9") (pinfunction "VDD1_G9_G9") (pintype "power_in"))
      (node (ref "U201") (pin "T4") (pinfunction "VDD1_T4_T4") (pintype "power_in"))
      (node (ref "U201") (pin "T9") (pinfunction "VDD1_T9_T9") (pintype "power_in"))
      (node (ref "U201") (pin "U1") (pinfunction "VDD1_U1_U1") (pintype "power_in"))
      (node (ref "U201") (pin "U12") (pinfunction "VDD1_U12_U12") (pintype "power_in"))
    )
    (net (code "41") (name "LPD4{slash}x_VDD2") (class "Default")
      (node (ref "C206") (pin "1") (pinfunction "1_1") (pintype "passive"))
      (node (ref "C207") (pin "1") (pinfunction "1_1") (pintype "passive"))
      (node (ref "C208") (pin "1") (pinfunction "1_1") (pintype "passive"))
      (node (ref "C210") (pin "1") (pinfunction "1_1") (pintype "passive"))
      (node (ref "C211") (pin "1") (pinfunction "1_1") (pintype "passive"))
      (node (ref "C212") (pin "1") (pinfunction "1_1") (pintype "passive"))
      (node (ref "C213") (pin "1") (pinfunction "1_1") (pintype "passive"))
      (node (ref "C214") (pin "1") (pinfunction "1_1") (pintype "passive"))
      (node (ref "R203") (pin "2") (pinfunction "2_2") (pintype "passive"))
      (node (ref "R210") (pin "1") (pinfunction "1_1") (pintype "passive"))
      (node (ref "U201") (pin "A4") (pinfunction "VDD2_A4_A4") (pintype "power_in"))
      (node (ref "U201") (pin "A9") (pinfunction "VDD2_A9_A9") (pintype "power_in"))
      (node (ref "U201") (pin "AB4") (pinfunction "VDD2_AB4_AB4") (pintype "power_in"))
      (node (ref "U201") (pin "AB9") (pinfunction "VDD2_AB9_AB9") (pintype "power_in"))
      (node (ref "U201") (pin "F5") (pinfunction "VDD2_F5_F5") (pintype "power_in"))
      (node (ref "U201") (pin "F8") (pinfunction "VDD2_F8_F8") (pintype "power_in"))
      (node (ref "U201") (pin "H1") (pinfunction "VDD2_H1_H1") (pintype "power_in"))
      (node (ref "U201") (pin "H12") (pinfunction "VDD2_H12_H12") (pintype "power_in"))
      (node (ref "U201") (pin "H5") (pinfunction "VDD2_H5_H5") (pintype "power_in"))
      (node (ref "U201") (pin "H8") (pinfunction "VDD2_H8_H8") (pintype "power_in"))
      (node (ref "U201") (pin "K1") (pinfunction "VDD2_K1_K1") (pintype "power_in"))
      (node (ref "U201") (pin "K10") (pinfunction "VDD2_K10_K10") (pintype "power_in"))
      (node (ref "U201") (pin "K12") (pinfunction "VDD2_K12_K12") (pintype "power_in"))
      (node (ref "U201") (pin "K3") (pinfunction "VDD2_K3_K3") (pintype "power_in"))
      (node (ref "U201") (pin "N1") (pinfunction "VDD2_N1_N1") (pintype "power_in"))
      (node (ref "U201") (pin "N10") (pinfunction "VDD2_N10_N10") (pintype "power_in"))
      (node (ref "U201") (pin "N12") (pinfunction "VDD2_N12_N12") (pintype "power_in"))
      (node (ref "U201") (pin "N3") (pinfunction "VDD2_N3_N3") (pintype "power_in"))
      (node (ref "U201") (pin "R1") (pinfunction "VDD2_R1_R1") (pintype "power_in"))
      (node (ref "U201") (pin "R12") (pinfunction "VDD2_R12_R12") (pintype "power_in"))
      (node (ref "U201") (pin "R5") (pinfunction "VDD2_R5_R5") (pintype "power_in"))
      (node (ref "U201") (pin "R8") (pinfunction "VDD2_R8_R8") (pintype "power_in"))
      (node (ref "U201") (pin "U5") (pinfunction "VDD2_U5_U5") (pintype "power_in"))
      (node (ref "U201") (pin "U8") (pinfunction "VDD2_U8_U8") (pintype "power_in"))
    )
    (net (code "42") (name "LPD4{slash}x_VDD2_1V1") (class "Default")
      (node (ref "R203") (pin "1") (pinfunction "1_1") (pintype "passive"))
    )
    (net (code "43") (name "LPD4{slash}x_VDDQ") (class "Default")
      (node (ref "C215") (pin "1") (pinfunction "1_1") (pintype "passive"))
      (node (ref "C216") (pin "1") (pinfunction "1_1") (pintype "passive"))
      (node (ref "C217") (pin "1") (pinfunction "1_1") (pintype "passive"))
      (node (ref "C218") (pin "1") (pinfunction "1_1") (pintype "passive"))
      (node (ref "C219") (pin "1") (pinfunction "1_1") (pintype "passive"))
      (node (ref "C220") (pin "1") (pinfunction "1_1") (pintype "passive"))
      (node (ref "C221") (pin "1") (pinfunction "1_1") (pintype "passive"))
      (node (ref "C222") (pin "1") (pinfunction "1_1") (pintype "passive"))
      (node (ref "R206") (pin "2") (pinfunction "2_2") (pintype "passive"))
      (node (ref "R209") (pin "1") (pinfunction "1_1") (pintype "passive"))
      (node (ref "U201") (pin "AA10") (pinfunction "VDDQ_AA10_AA10") (pintype "power_in"))
      (node (ref "U201") (pin "AA3") (pinfunction "VDDQ_AA3_AA3") (pintype "power_in"))
      (node (ref "U201") (pin "AA5") (pinfunction "VDDQ_AA5_AA5") (pintype "power_in"))
      (node (ref "U201") (pin "AA8") (pinfunction "VDDQ_AA8_AA8") (pintype "power_in"))
      (node (ref "U201") (pin "B10") (pinfunction "VDDQ_B10_B10") (pintype "power_in"))
      (node (ref "U201") (pin "B3") (pinfunction "VDDQ_B3_B3") (pintype "power_in"))
      (node (ref "U201") (pin "B5") (pinfunction "VDDQ_B5_B5") (pintype "power_in"))
      (node (ref "U201") (pin "B8") (pinfunction "VDDQ_B8_B8") (pintype "power_in"))
      (node (ref "U201") (pin "D1") (pinfunction "VDDQ_D1_D1") (pintype "power_in"))
      (node (ref "U201") (pin "D12") (pinfunction "VDDQ_D12_D12") (pintype "power_in"))
      (node (ref "U201") (pin "D5") (pinfunction "VDDQ_D5_D5") (pintype "power_in"))
      (node (ref "U201") (pin "D8") (pinfunction "VDDQ_D8_D8") (pintype "power_in"))
      (node (ref "U201") (pin "F10") (pinfunction "VDDQ_F10_F10") (pintype "power_in"))
      (node (ref "U201") (pin "F3") (pinfunction "VDDQ_F3_F3") (pintype "power_in"))
      (node (ref "U201") (pin "U10") (pinfunction "VDDQ_U10_U10") (pintype "power_in"))
      (node (ref "U201") (pin "U3") (pinfunction "VDDQ_U3_U3") (pintype "power_in"))
      (node (ref "U201") (pin "W1") (pinfunction "VDDQ_W1_W1") (pintype "power_in"))
      (node (ref "U201") (pin "W12") (pinfunction "VDDQ_W12_W12") (pintype "power_in"))
      (node (ref "U201") (pin "W5") (pinfunction "VDDQ_W5_W5") (pintype "power_in"))
      (node (ref "U201") (pin "W8") (pinfunction "VDDQ_W8_W8") (pintype "power_in"))
    )
    (net (code "44") (name "LPD4{slash}x_VDDQ_0V6") (class "Default")
      (node (ref "R206") (pin "1") (pinfunction "1_1") (pintype "passive"))
    )
    (net (code "45") (name "Net-(TP202-Pin1)") (class "Default")
      (node (ref "TP202") (pin "1") (pinfunction "Pin1_1") (pintype "passive"))
      (node (ref "U101") (pin "D4") (pinfunction "DRAM_MTEST1_D4") (pintype "passive"))
    )
    (net (code "46") (name "VDD_1V8") (class "Default")
      (node (ref "R202") (pin "1") (pinfunction "1_1") (pintype "passive"))
    )
    (net (code "47") (name "unconnected-(U201A-CA0_B-PadR2)") (class "Default")
      (node (ref "U201") (pin "R2") (pinfunction "CA0_B_R2") (pintype "input"))
    )
    (net (code "48") (name "unconnected-(U201A-CA1_B-PadP2)") (class "Default")
      (node (ref "U201") (pin "P2") (pinfunction "CA1_B_P2") (pintype "input"))
    )
    (net (code "49") (name "unconnected-(U201A-CA2_B-PadR9)") (class "Default")
      (node (ref "U201") (pin "R9") (pinfunction "CA2_B_R9") (pintype "input"))
    )
    (net (code "50") (name "unconnected-(U201A-CA3_B-PadR10)") (class "Default")
      (node (ref "U201") (pin "R10") (pinfunction "CA3_B_R10") (pintype "input"))
    )
    (net (code "51") (name "unconnected-(U201A-CA4_B-PadR11)") (class "Default")
      (node (ref "U201") (pin "R11") (pinfunction "CA4_B_R11") (pintype "input"))
    )
    (net (code "52") (name "unconnected-(U201A-CA5_B-PadP11)") (class "Default")
      (node (ref "U201") (pin "P11") (pinfunction "CA5_B_P11") (pintype "input"))
    )
    (net (code "53") (name "unconnected-(U201A-CKE0_B-PadP4)") (class "Default")
      (node (ref "U201") (pin "P4") (pinfunction "CKE0_B_P4") (pintype "input"))
    )
    (net (code "54") (name "unconnected-(U201A-CKE1_B-PadP5)") (class "Default")
      (node (ref "U201") (pin "P5") (pinfunction "CKE1_B_P5") (pintype "input"))
    )
    (net (code "55") (name "unconnected-(U201A-CK_c_B-PadP9)") (class "Default")
      (node (ref "U201") (pin "P9") (pinfunction "CK_c_B_P9") (pintype "input"))
    )
    (net (code "56") (name "unconnected-(U201A-CK_t_B-PadP8)") (class "Default")
      (node (ref "U201") (pin "P8") (pinfunction "CK_t_B_P8") (pintype "input"))
    )
    (net (code "57") (name "unconnected-(U201A-CS0_B-PadR4)") (class "Default")
      (node (ref "U201") (pin "R4") (pinfunction "CS0_B_R4") (pintype "input"))
    )
    (net (code "58") (name "unconnected-(U201A-CS1_B-PadR3)") (class "Default")
      (node (ref "U201") (pin "R3") (pinfunction "CS1_B_R3") (pintype "input"))
    )
    (net (code "59") (name "unconnected-(U201A-DMI0_B-PadY3)") (class "Default")
      (node (ref "U201") (pin "Y3") (pinfunction "DMI0_B_Y3") (pintype "bidirectional"))
    )
    (net (code "60") (name "unconnected-(U201A-DMI1_B-PadY10)") (class "Default")
      (node (ref "U201") (pin "Y10") (pinfunction "DMI1_B_Y10") (pintype "bidirectional"))
    )
    (net (code "61") (name "unconnected-(U201A-DNU_A1-PadA1)") (class "Default")
      (node (ref "U201") (pin "A1") (pinfunction "DNU_A1_A1") (pintype "passive+no_connect"))
    )
    (net (code "62") (name "unconnected-(U201A-DNU_A2-PadA2)") (class "Default")
      (node (ref "U201") (pin "A2") (pinfunction "DNU_A2_A2") (pintype "passive+no_connect"))
    )
    (net (code "63") (name "unconnected-(U201A-DNU_A11-PadA11)") (class "Default")
      (node (ref "U201") (pin "A11") (pinfunction "DNU_A11_A11") (pintype "passive+no_connect"))
    )
    (net (code "64") (name "unconnected-(U201A-DNU_A12-PadA12)") (class "Default")
      (node (ref "U201") (pin "A12") (pinfunction "DNU_A12_A12") (pintype "passive+no_connect"))
    )
    (net (code "65") (name "unconnected-(U201A-DNU_AA1-PadAA1)") (class "Default")
      (node (ref "U201") (pin "AA1") (pinfunction "DNU_AA1_AA1") (pintype "passive+no_connect"))
    )
    (net (code "66") (name "unconnected-(U201A-DNU_AA12-PadAA12)") (class "Default")
      (node (ref "U201") (pin "AA12") (pinfunction "DNU_AA12_AA12") (pintype "passive+no_connect"))
    )
    (net (code "67") (name "unconnected-(U201A-DNU_AB1-PadAB1)") (class "Default")
      (node (ref "U201") (pin "AB1") (pinfunction "DNU_AB1_AB1") (pintype "passive+no_connect"))
    )
    (net (code "68") (name "unconnected-(U201A-DNU_AB2-PadAB2)") (class "Default")
      (node (ref "U201") (pin "AB2") (pinfunction "DNU_AB2_AB2") (pintype "passive+no_connect"))
    )
    (net (code "69") (name "unconnected-(U201A-DNU_AB11-PadAB11)") (class "Default")
      (node (ref "U201") (pin "AB11") (pinfunction "DNU_AB11_AB11") (pintype "passive+no_connect"))
    )
    (net (code "70") (name "unconnected-(U201A-DNU_AB12-PadAB12)") (class "Default")
      (node (ref "U201") (pin "AB12") (pinfunction "DNU_AB12_AB12") (pintype "passive+no_connect"))
    )
    (net (code "71") (name "unconnected-(U201A-DNU_B1-PadB1)") (class "Default")
      (node (ref "U201") (pin "B1") (pinfunction "DNU_B1_B1") (pintype "passive+no_connect"))
    )
    (net (code "72") (name "unconnected-(U201A-DNU_B12-PadB12)") (class "Default")
      (node (ref "U201") (pin "B12") (pinfunction "DNU_B12_B12") (pintype "passive+no_connect"))
    )
    (net (code "73") (name "unconnected-(U201A-DQ0_B-PadAA2)") (class "Default")
      (node (ref "U201") (pin "AA2") (pinfunction "DQ0_B_AA2") (pintype "bidirectional"))
    )
    (net (code "74") (name "unconnected-(U201A-DQ1_B-PadY2)") (class "Default")
      (node (ref "U201") (pin "Y2") (pinfunction "DQ1_B_Y2") (pintype "bidirectional"))
    )
    (net (code "75") (name "unconnected-(U201A-DQ2_B-PadV2)") (class "Default")
      (node (ref "U201") (pin "V2") (pinfunction "DQ2_B_V2") (pintype "bidirectional"))
    )
    (net (code "76") (name "unconnected-(U201A-DQ3_B-PadU2)") (class "Default")
      (node (ref "U201") (pin "U2") (pinfunction "DQ3_B_U2") (pintype "bidirectional"))
    )
    (net (code "77") (name "unconnected-(U201A-DQ4_B-PadU4)") (class "Default")
      (node (ref "U201") (pin "U4") (pinfunction "DQ4_B_U4") (pintype "bidirectional"))
    )
    (net (code "78") (name "unconnected-(U201A-DQ5_B-PadV4)") (class "Default")
      (node (ref "U201") (pin "V4") (pinfunction "DQ5_B_V4") (pintype "bidirectional"))
    )
    (net (code "79") (name "unconnected-(U201A-DQ6_B-PadY4)") (class "Default")
      (node (ref "U201") (pin "Y4") (pinfunction "DQ6_B_Y4") (pintype "bidirectional"))
    )
    (net (code "80") (name "unconnected-(U201A-DQ7_B-PadAA4)") (class "Default")
      (node (ref "U201") (pin "AA4") (pinfunction "DQ7_B_AA4") (pintype "bidirectional"))
    )
    (net (code "81") (name "unconnected-(U201A-DQ8_B-PadAA11)") (class "Default")
      (node (ref "U201") (pin "AA11") (pinfunction "DQ8_B_AA11") (pintype "bidirectional"))
    )
    (net (code "82") (name "unconnected-(U201A-DQ9_B-PadY11)") (class "Default")
      (node (ref "U201") (pin "Y11") (pinfunction "DQ9_B_Y11") (pintype "bidirectional"))
    )
    (net (code "83") (name "unconnected-(U201A-DQ10_B-PadV11)") (class "Default")
      (node (ref "U201") (pin "V11") (pinfunction "DQ10_B_V11") (pintype "bidirectional"))
    )
    (net (code "84") (name "unconnected-(U201A-DQ11_B-PadU11)") (class "Default")
      (node (ref "U201") (pin "U11") (pinfunction "DQ11_B_U11") (pintype "bidirectional"))
    )
    (net (code "85") (name "unconnected-(U201A-DQ12_B-PadU9)") (class "Default")
      (node (ref "U201") (pin "U9") (pinfunction "DQ12_B_U9") (pintype "bidirectional"))
    )
    (net (code "86") (name "unconnected-(U201A-DQ13_B-PadV9)") (class "Default")
      (node (ref "U201") (pin "V9") (pinfunction "DQ13_B_V9") (pintype "bidirectional"))
    )
    (net (code "87") (name "unconnected-(U201A-DQ14_B-PadY9)") (class "Default")
      (node (ref "U201") (pin "Y9") (pinfunction "DQ14_B_Y9") (pintype "bidirectional"))
    )
    (net (code "88") (name "unconnected-(U201A-DQ15_B-PadAA9)") (class "Default")
      (node (ref "U201") (pin "AA9") (pinfunction "DQ15_B_AA9") (pintype "bidirectional"))
    )
    (net (code "89") (name "unconnected-(U201A-DQS0_c_B-PadV3)") (class "Default")
      (node (ref "U201") (pin "V3") (pinfunction "DQS0_c_B_V3") (pintype "bidirectional"))
    )
    (net (code "90") (name "unconnected-(U201A-DQS0_t_B-PadW3)") (class "Default")
      (node (ref "U201") (pin "W3") (pinfunction "DQS0_t_B_W3") (pintype "bidirectional"))
    )
    (net (code "91") (name "unconnected-(U201A-DQS1_c_B-PadV10)") (class "Default")
      (node (ref "U201") (pin "V10") (pinfunction "DQS1_c_B_V10") (pintype "bidirectional"))
    )
    (net (code "92") (name "unconnected-(U201A-DQS1_t_B-PadW10)") (class "Default")
      (node (ref "U201") (pin "W10") (pinfunction "DQS1_t_B_W10") (pintype "bidirectional"))
    )
    (net (code "93") (name "unconnected-(U201A-NC_G11-PadG11)") (class "Default")
      (node (ref "U201") (pin "G11") (pinfunction "NC_G11_G11") (pintype "passive+no_connect"))
    )
    (net (code "94") (name "unconnected-(U201A-NC_K5-PadK5)") (class "Default")
      (node (ref "U201") (pin "K5") (pinfunction "NC_K5_K5") (pintype "passive+no_connect"))
    )
    (net (code "95") (name "unconnected-(U201A-NC_K8-PadK8)") (class "Default")
      (node (ref "U201") (pin "K8") (pinfunction "NC_K8_K8") (pintype "passive+no_connect"))
    )
    (net (code "96") (name "unconnected-(U201A-NC_N5-PadN5)") (class "Default")
      (node (ref "U201") (pin "N5") (pinfunction "NC_N5_N5") (pintype "passive+no_connect"))
    )
    (net (code "97") (name "unconnected-(U201A-NC_N8-PadN8)") (class "Default")
      (node (ref "U201") (pin "N8") (pinfunction "NC_N8_N8") (pintype "passive+no_connect"))
    )
    (net (code "98") (name "unconnected-(U201A-ODT_CA_B-PadT2)") (class "Default")
      (node (ref "U201") (pin "T2") (pinfunction "ODT_CA_B_T2") (pintype "input"))
    )
    (net (code "99") (name "unconnected-(U201A-ZQ1-PadA8)") (class "Default")
      (node (ref "U201") (pin "A8") (pinfunction "ZQ1_A8") (pintype "passive"))
    )
  )
)
